# CircuitSchematic.net
KiCad netlist of a schematic drawn in EAGLE
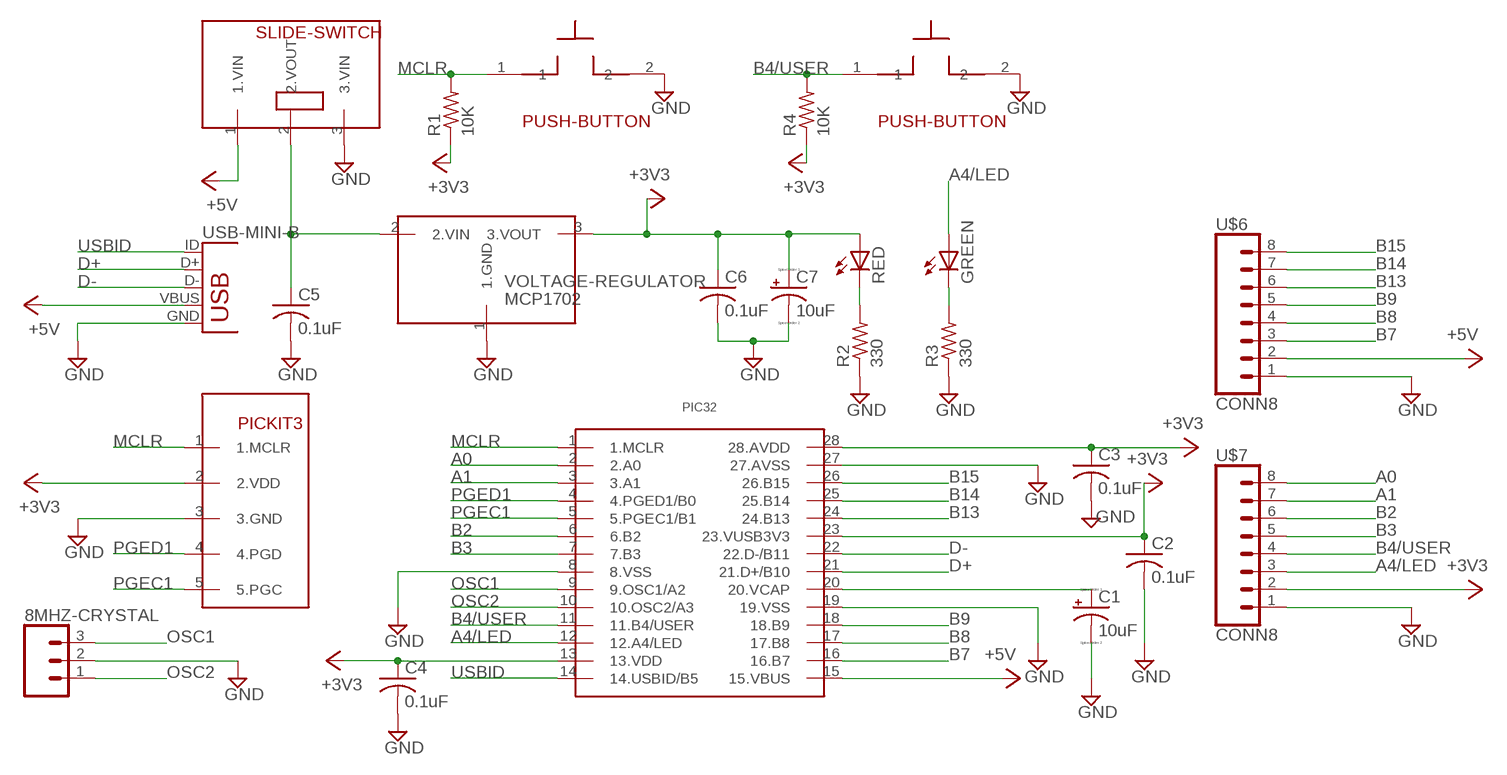
[diagram p0: schematic, sheet 1]

(export (version "E")
  (design (tool "Eeschema 10.0.6"))
  (components
    (comp (ref "8MHZ-CRYSTAL")
      (value "CONN_03")
      (footprint "eagle-import:1X03")
      (libsource (lib "eagle-import") (part "CONN_03"))
    )
    (comp (ref "C1")
      (value "10uF")
      (footprint "eagle-import:E5-5")
      (libsource (lib "eagle-import") (part "CPOL-USE5-5"))
    )
    (comp (ref "C2")
      (value "0.1uF")
      (footprint "eagle-import:C025-025X050")
      (libsource (lib "eagle-import") (part "C-US025-025X050"))
    )
    (comp (ref "C3")
      (value "0.1uF")
      (footprint "eagle-import:C025-025X050")
      (libsource (lib "eagle-import") (part "C-US025-025X050"))
    )
    (comp (ref "C4")
      (value "0.1uF")
      (footprint "eagle-import:C025-025X050")
      (libsource (lib "eagle-import") (part "C-US025-025X050"))
    )
    (comp (ref "C5")
      (value "0.1uF")
      (footprint "eagle-import:C025-025X050")
      (libsource (lib "eagle-import") (part "C-US025-025X050"))
    )
    (comp (ref "C6")
      (value "0.1uF")
      (footprint "eagle-import:C025-025X050")
      (libsource (lib "eagle-import") (part "C-US025-025X050"))
    )
    (comp (ref "C7")
      (value "10uF")
      (footprint "eagle-import:E5-5")
      (libsource (lib "eagle-import") (part "CPOL-USE5-5"))
    )
    (comp (ref "GREEN")
      (value "LED3MM")
      (footprint "eagle-import:LED3MM")
      (libsource (lib "eagle-import") (part "LED3MM"))
    )
    (comp (ref "R1")
      (value "10K")
      (footprint "eagle-import:0207_10")
      (libsource (lib "eagle-import") (part "R-US_0207/10"))
    )
    (comp (ref "R2")
      (value "330")
      (footprint "eagle-import:0207_10")
      (libsource (lib "eagle-import") (part "R-US_0207/10"))
    )
    (comp (ref "R3")
      (value "330")
      (footprint "eagle-import:0207_10")
      (libsource (lib "eagle-import") (part "R-US_0207/10"))
    )
    (comp (ref "R4")
      (value "10K")
      (footprint "eagle-import:0207_10")
      (libsource (lib "eagle-import") (part "R-US_0207/10"))
    )
    (comp (ref "RED")
      (value "LED3MM")
      (footprint "eagle-import:LED3MM")
      (libsource (lib "eagle-import") (part "LED3MM"))
    )
    (comp (ref "U$1")
      (value "SLIDE-SWITCH")
      (footprint "eagle-import:SLIDE-SWITCH-2")
      (libsource (lib "eagle-import") (part "SLIDE-SWITCH"))
    )
    (comp (ref "U$2")
      (value "PUSH-BUTTON")
      (footprint "eagle-import:PUSH-BUTTON")
      (libsource (lib "eagle-import") (part "PUSH-BUTTON"))
    )
    (comp (ref "U$3")
      (value "PUSH-BUTTON")
      (footprint "eagle-import:PUSH-BUTTON")
      (libsource (lib "eagle-import") (part "PUSH-BUTTON"))
    )
    (comp (ref "U$4")
      (value "PIC32")
      (footprint "eagle-import:DIP28")
      (libsource (lib "eagle-import") (part "PIC32"))
    )
    (comp (ref "U$5")
      (value "PICKIT3")
      (footprint "eagle-import:PICKIT3")
      (libsource (lib "eagle-import") (part "PICKIT3"))
    )
    (comp (ref "U$6")
      (value "CONN8")
      (footprint "eagle-import:CONN8")
      (libsource (lib "eagle-import") (part "CONN8"))
    )
    (comp (ref "U$7")
      (value "CONN8")
      (footprint "eagle-import:CONN8")
      (libsource (lib "eagle-import") (part "CONN8"))
    )
    (comp (ref "USB-MINI-B")
      (value "USB-MB-H")
      (footprint "eagle-import:USB-MB-H")
      (libsource (lib "eagle-import") (part "USB-MB-H"))
    )
    (comp (ref "VOLTAGE-REGULATOR")
      (value "MCP1702")
      (footprint "eagle-import:TO92")
      (libsource (lib "eagle-import") (part "MCP1702"))
    )
  )
  (nets
    (net (code "1") (name "+3V3") (class "Default")
      (node (ref "C2") (pin "1") (pinfunction "1_1") (pintype "passive"))
      (node (ref "C3") (pin "1") (pinfunction "1_1") (pintype "passive"))
      (node (ref "C4") (pin "1") (pinfunction "1_1") (pintype "passive"))
      (node (ref "C6") (pin "1") (pinfunction "1_1") (pintype "passive"))
      (node (ref "C7") (pin "+") (pinfunction "+_+") (pintype "passive"))
      (node (ref "R1") (pin "1") (pinfunction "1_1") (pintype "passive"))
      (node (ref "R4") (pin "1") (pinfunction "1_1") (pintype "passive"))
      (node (ref "RED") (pin "A") (pinfunction "A_A") (pintype "passive"))
      (node (ref "U$4") (pin "13") (pinfunction "13.VDD_13") (pintype "bidirectional"))
      (node (ref "U$4") (pin "23") (pinfunction "23.VUSB3V3_23") (pintype "bidirectional"))
      (node (ref "U$4") (pin "28") (pinfunction "28.AVDD_28") (pintype "bidirectional"))
      (node (ref "U$5") (pin "2") (pinfunction "2.VDD_2") (pintype "bidirectional"))
      (node (ref "U$7") (pin "2") (pinfunction "2_2") (pintype "passive"))
      (node (ref "VOLTAGE-REGULATOR") (pin "3") (pinfunction "3.VOUT_3") (pintype "bidirectional"))
    )
    (net (code "2") (name "+5V") (class "Default")
      (node (ref "U$1") (pin "1") (pinfunction "1.VIN_1") (pintype "bidirectional"))
      (node (ref "U$4") (pin "15") (pinfunction "15.VBUS_15") (pintype "bidirectional"))
      (node (ref "U$6") (pin "2") (pinfunction "2_2") (pintype "passive"))
      (node (ref "USB-MINI-B") (pin "VBUS") (pinfunction "VBUS_VBUS") (pintype "bidirectional"))
    )
    (net (code "3") (name "/A0") (class "Default")
      (node (ref "U$4") (pin "2") (pinfunction "2.A0_2") (pintype "bidirectional"))
      (node (ref "U$7") (pin "8") (pinfunction "8_8") (pintype "passive"))
    )
    (net (code "4") (name "/A1") (class "Default")
      (node (ref "U$4") (pin "3") (pinfunction "3.A1_3") (pintype "bidirectional"))
      (node (ref "U$7") (pin "7") (pinfunction "7_7") (pintype "passive"))
    )
    (net (code "5") (name "/A4{slash}LED") (class "Default")
      (node (ref "GREEN") (pin "A") (pinfunction "A_A") (pintype "passive"))
      (node (ref "U$4") (pin "12") (pinfunction "12.A4/LED_12") (pintype "bidirectional"))
      (node (ref "U$7") (pin "3") (pinfunction "3_3") (pintype "passive"))
    )
    (net (code "6") (name "/B2") (class "Default")
      (node (ref "U$4") (pin "6") (pinfunction "6.B2_6") (pintype "bidirectional"))
      (node (ref "U$7") (pin "6") (pinfunction "6_6") (pintype "passive"))
    )
    (net (code "7") (name "/B3") (class "Default")
      (node (ref "U$4") (pin "7") (pinfunction "7.B3_7") (pintype "bidirectional"))
      (node (ref "U$7") (pin "5") (pinfunction "5_5") (pintype "passive"))
    )
    (net (code "8") (name "/B4{slash}USER") (class "Default")
      (node (ref "R4") (pin "2") (pinfunction "2_2") (pintype "passive"))
      (node (ref "U$3") (pin "1") (pinfunction "1_1") (pintype "bidirectional"))
      (node (ref "U$4") (pin "11") (pinfunction "11.B4/USER_11") (pintype "bidirectional"))
      (node (ref "U$7") (pin "4") (pinfunction "4_4") (pintype "passive"))
    )
    (net (code "9") (name "/B7") (class "Default")
      (node (ref "U$4") (pin "16") (pinfunction "16.B7_16") (pintype "bidirectional"))
      (node (ref "U$6") (pin "3") (pinfunction "3_3") (pintype "passive"))
    )
    (net (code "10") (name "/B8") (class "Default")
      (node (ref "U$4") (pin "17") (pinfunction "17.B8_17") (pintype "bidirectional"))
      (node (ref "U$6") (pin "4") (pinfunction "4_4") (pintype "passive"))
    )
    (net (code "11") (name "/B9") (class "Default")
      (node (ref "U$4") (pin "18") (pinfunction "18.B9_18") (pintype "bidirectional"))
      (node (ref "U$6") (pin "5") (pinfunction "5_5") (pintype "passive"))
    )
    (net (code "12") (name "/B13") (class "Default")
      (node (ref "U$4") (pin "24") (pinfunction "24.B13_24") (pintype "bidirectional"))
      (node (ref "U$6") (pin "6") (pinfunction "6_6") (pintype "passive"))
    )
    (net (code "13") (name "/B14") (class "Default")
      (node (ref "U$4") (pin "25") (pinfunction "25.B14_25") (pintype "bidirectional"))
      (node (ref "U$6") (pin "7") (pinfunction "7_7") (pintype "passive"))
    )
    (net (code "14") (name "/B15") (class "Default")
      (node (ref "U$4") (pin "26") (pinfunction "26.B15_26") (pintype "bidirectional"))
      (node (ref "U$6") (pin "8") (pinfunction "8_8") (pintype "passive"))
    )
    (net (code "15") (name "/D+") (class "Default")
      (node (ref "U$4") (pin "21") (pinfunction "21.D+/B10_21") (pintype "bidirectional"))
      (node (ref "USB-MINI-B") (pin "D+") (pinfunction "D+_D+") (pintype "bidirectional"))
    )
    (net (code "16") (name "/D-") (class "Default")
      (node (ref "U$4") (pin "22") (pinfunction "22.D-/B11_22") (pintype "bidirectional"))
      (node (ref "USB-MINI-B") (pin "D-") (pinfunction "D-_D-") (pintype "bidirectional"))
    )
    (net (code "17") (name "/MCLR") (class "Default")
      (node (ref "R1") (pin "2") (pinfunction "2_2") (pintype "passive"))
      (node (ref "U$2") (pin "1") (pinfunction "1_1") (pintype "bidirectional"))
      (node (ref "U$4") (pin "1") (pinfunction "1.MCLR_1") (pintype "bidirectional"))
      (node (ref "U$5") (pin "1") (pinfunction "1.MCLR_1") (pintype "bidirectional"))
    )
    (net (code "18") (name "/OSC1") (class "Default")
      (node (ref "8MHZ-CRYSTAL") (pin "3") (pinfunction "3_3") (pintype "passive"))
      (node (ref "U$4") (pin "9") (pinfunction "9.OSC1/A2_9") (pintype "bidirectional"))
    )
    (net (code "19") (name "/OSC2") (class "Default")
      (node (ref "8MHZ-CRYSTAL") (pin "1") (pinfunction "1_1") (pintype "passive"))
      (node (ref "U$4") (pin "10") (pinfunction "10.OSC2/A3_10") (pintype "bidirectional"))
    )
    (net (code "20") (name "/PGEC1") (class "Default")
      (node (ref "U$4") (pin "5") (pinfunction "5.PGEC1/B1_5") (pintype "bidirectional"))
      (node (ref "U$5") (pin "5") (pinfunction "5.PGC_5") (pintype "bidirectional"))
    )
    (net (code "21") (name "/PGED1") (class "Default")
      (node (ref "U$4") (pin "4") (pinfunction "4.PGED1/B0_4") (pintype "bidirectional"))
      (node (ref "U$5") (pin "4") (pinfunction "4.PGD_4") (pintype "bidirectional"))
    )
    (net (code "22") (name "/USBID") (class "Default")
      (node (ref "U$4") (pin "14") (pinfunction "14.USBID/B5_14") (pintype "bidirectional"))
      (node (ref "USB-MINI-B") (pin "ID") (pinfunction "ID_ID") (pintype "bidirectional"))
    )
    (net (code "23") (name "GND") (class "Default")
      (node (ref "8MHZ-CRYSTAL") (pin "2") (pinfunction "2_2") (pintype "passive"))
      (node (ref "C1") (pin "-") (pinfunction "-_-") (pintype "passive"))
      (node (ref "C2") (pin "2") (pinfunction "2_2") (pintype "passive"))
      (node (ref "C3") (pin "2") (pinfunction "2_2") (pintype "passive"))
      (node (ref "C4") (pin "2") (pinfunction "2_2") (pintype "passive"))
      (node (ref "C5") (pin "2") (pinfunction "2_2") (pintype "passive"))
      (node (ref "C6") (pin "2") (pinfunction "2_2") (pintype "passive"))
      (node (ref "C7") (pin "-") (pinfunction "-_-") (pintype "passive"))
      (node (ref "R2") (pin "1") (pinfunction "1_1") (pintype "passive"))
      (node (ref "R3") (pin "1") (pinfunction "1_1") (pintype "passive"))
      (node (ref "U$1") (pin "3") (pinfunction "3.VIN_3") (pintype "bidirectional"))
      (node (ref "U$2") (pin "2") (pinfunction "2_2") (pintype "bidirectional"))
      (node (ref "U$3") (pin "2") (pinfunction "2_2") (pintype "bidirectional"))
      (node (ref "U$4") (pin "19") (pinfunction "19.VSS_19") (pintype "bidirectional"))
      (node (ref "U$4") (pin "27") (pinfunction "27.AVSS_27") (pintype "bidirectional"))
      (node (ref "U$4") (pin "8") (pinfunction "8.VSS_8") (pintype "bidirectional"))
      (node (ref "U$5") (pin "3") (pinfunction "3.GND_3") (pintype "bidirectional"))
      (node (ref "U$6") (pin "1") (pinfunction "1_1") (pintype "passive"))
      (node (ref "U$7") (pin "1") (pinfunction "1_1") (pintype "passive"))
      (node (ref "USB-MINI-B") (pin "GND") (pinfunction "GND_GND") (pintype "bidirectional"))
      (node (ref "VOLTAGE-REGULATOR") (pin "1") (pinfunction "1.GND_1") (pintype "bidirectional"))
    )
    (net (code "24") (name "Net-(GREEN-C)") (class "Default")
      (node (ref "GREEN") (pin "K") (pinfunction "C_K") (pintype "passive"))
      (node (ref "R3") (pin "2") (pinfunction "2_2") (pintype "passive"))
    )
    (net (code "25") (name "Net-(RED-C)") (class "Default")
      (node (ref "R2") (pin "2") (pinfunction "2_2") (pintype "passive"))
      (node (ref "RED") (pin "K") (pinfunction "C_K") (pintype "passive"))
    )
    (net (code "26") (name "Net-(U$1-2.VOUT)") (class "Default")
      (node (ref "C5") (pin "1") (pinfunction "1_1") (pintype "passive"))
      (node (ref "U$1") (pin "2") (pinfunction "2.VOUT_2") (pintype "bidirectional"))
      (node (ref "VOLTAGE-REGULATOR") (pin "2") (pinfunction "2.VIN_2") (pintype "bidirectional"))
    )
    (net (code "27") (name "Net-(U$4-20.VCAP)") (class "Default")
      (node (ref "C1") (pin "+") (pinfunction "+_+") (pintype "passive"))
      (node (ref "U$4") (pin "20") (pinfunction "20.VCAP_20") (pintype "bidirectional"))
    )
  )
)
